# 1_V1.net
KiCad netlist of a schematic drawn in Altium Designer
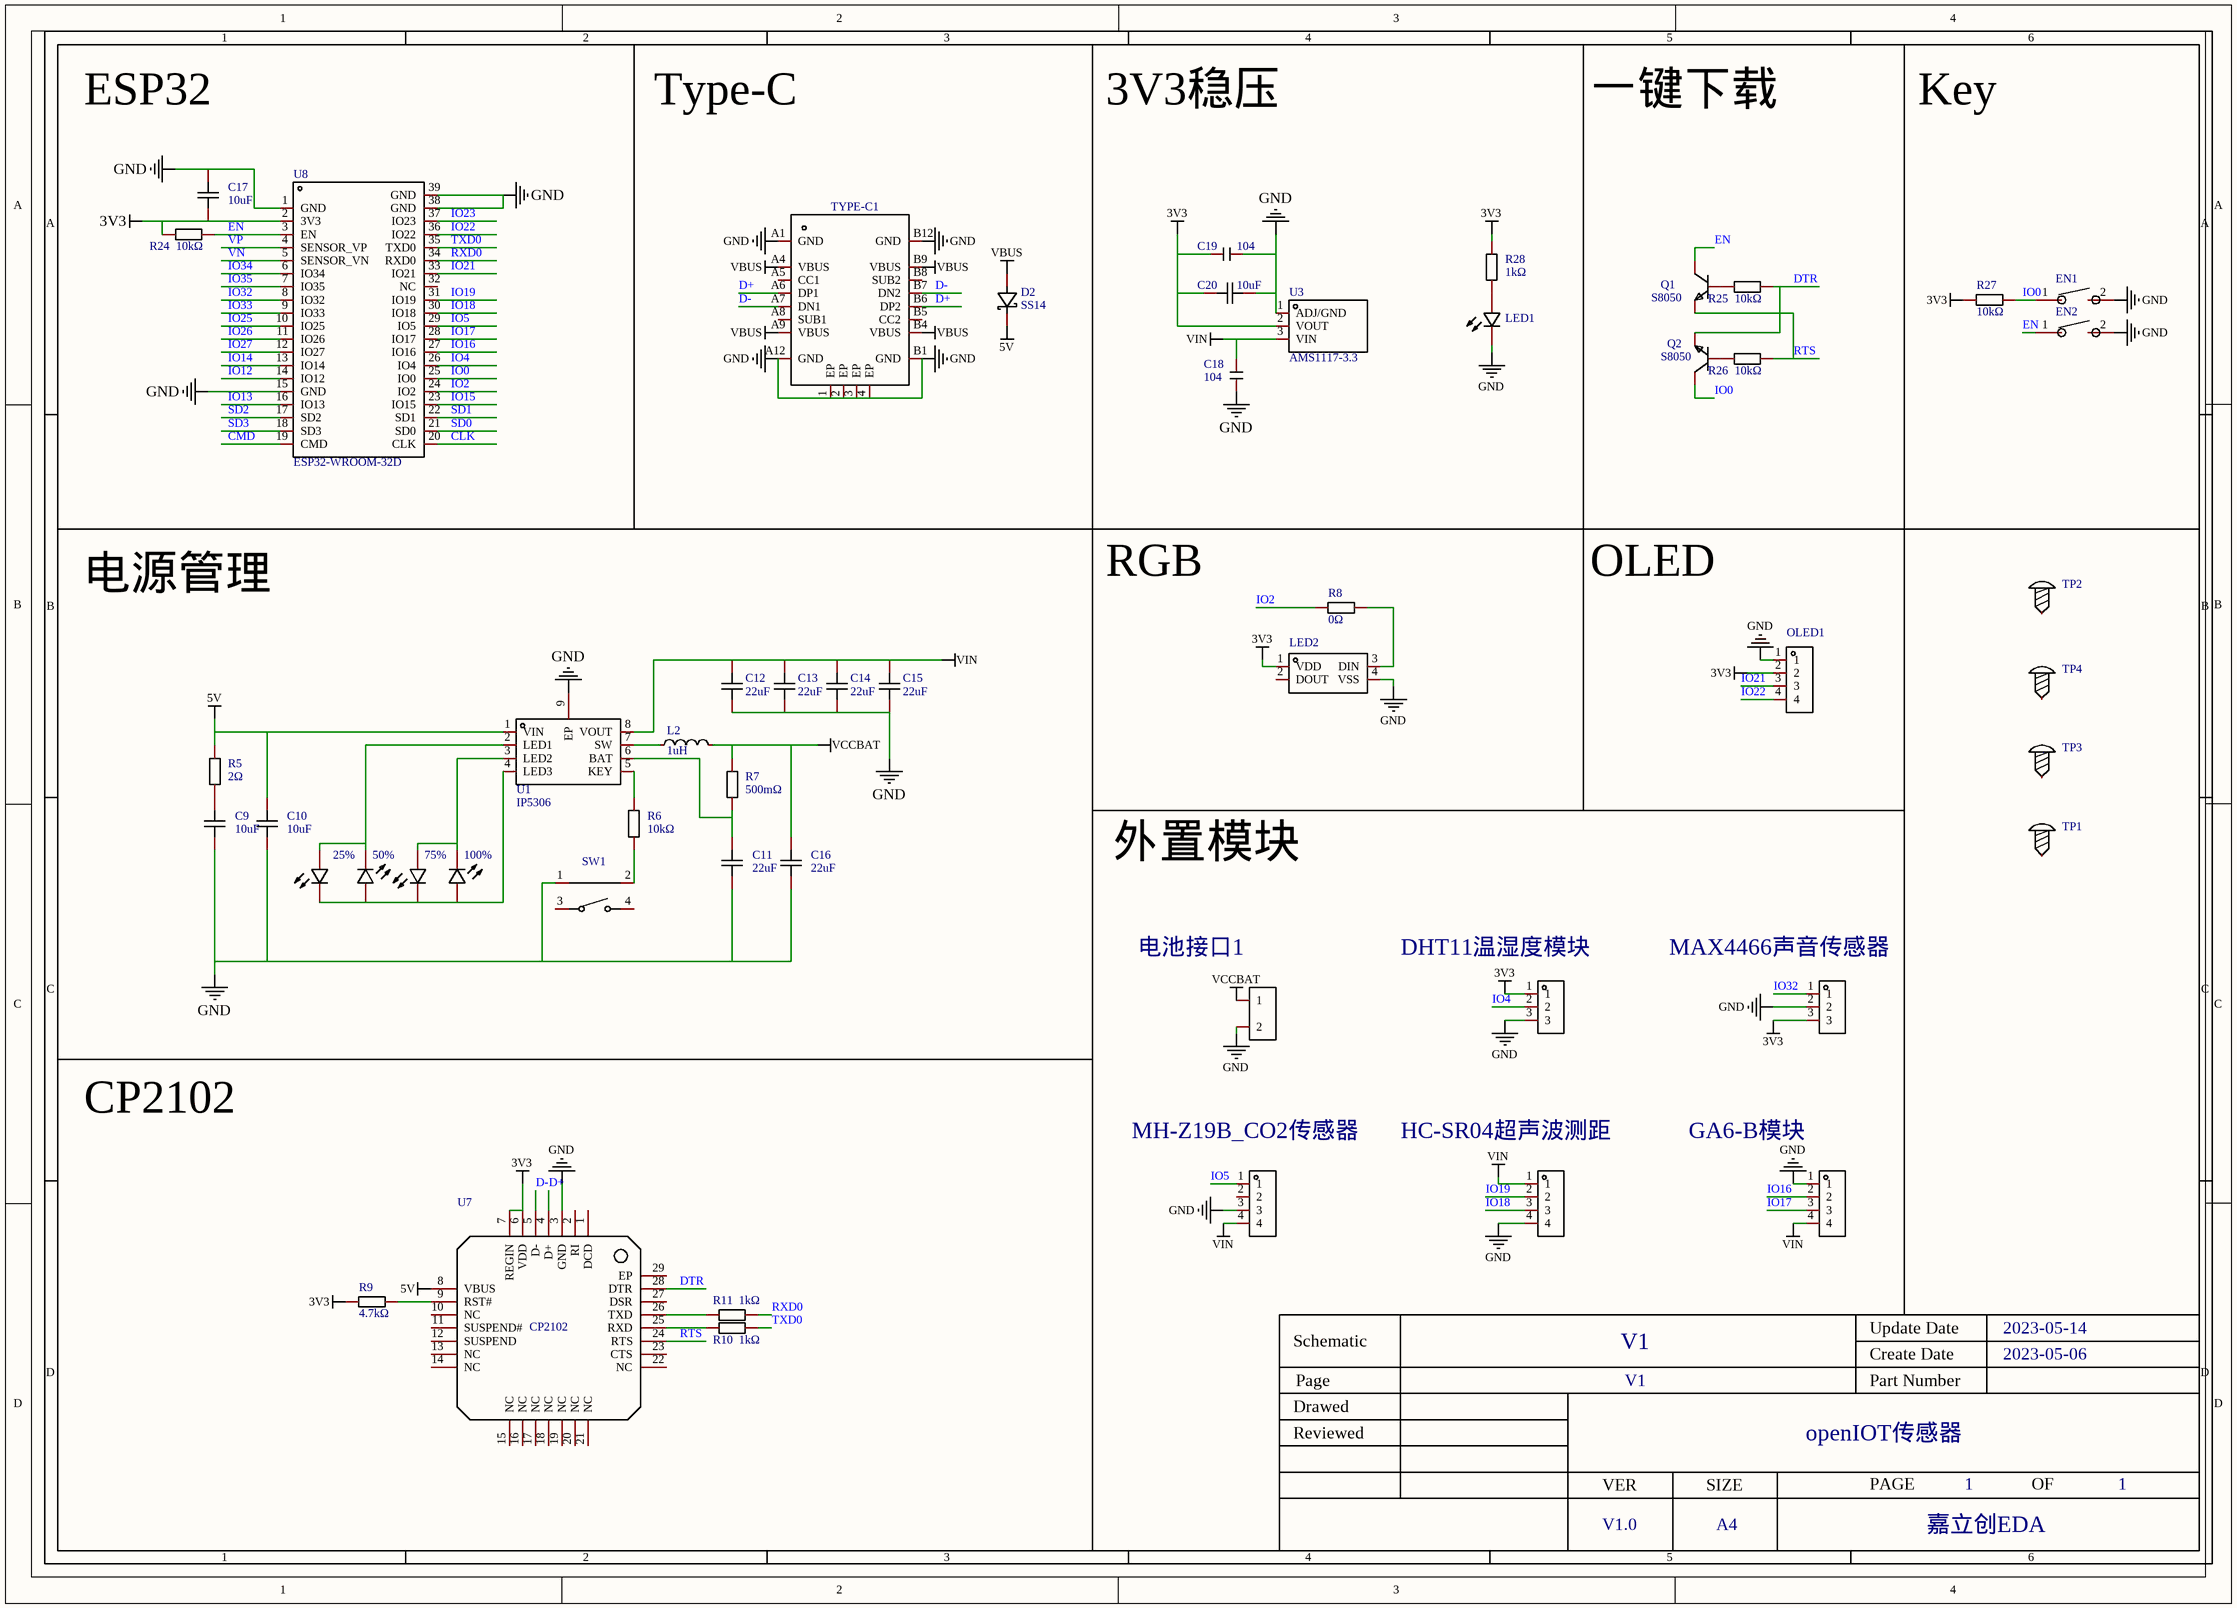
[diagram p0: 1_V1.schdoc]

(export (version "E")
  (design (tool "Eeschema 10.0.6"))
  (components
    (comp (ref "25%")
      (value "19-217/GHC-YR1S2/3T")
      (description "发光颜色:翠绿;二极管配置:-;主波长:520nm~535nm;色温:-;功率:110mW;安装方式:-;")
      (fields (field (name "MANUFACTURER") "EVERLIGHT(亿光)"))
      (libsource (lib "altium-import") (part "root_1_19-217/GHC-YR1S2/3T_"))
    )
    (comp (ref "50%")
      (value "19-217/GHC-YR1S2/3T")
      (description "发光颜色:翠绿;二极管配置:-;主波长:520nm~535nm;色温:-;功率:110mW;安装方式:-;")
      (fields (field (name "MANUFACTURER") "EVERLIGHT(亿光)"))
      (libsource (lib "altium-import") (part "root_3_19-217/GHC-YR1S2/3T_"))
    )
    (comp (ref "75%")
      (value "19-217/GHC-YR1S2/3T")
      (description "发光颜色:翠绿;二极管配置:-;主波长:520nm~535nm;色温:-;功率:110mW;安装方式:-;")
      (fields (field (name "MANUFACTURER") "EVERLIGHT(亿光)"))
      (libsource (lib "altium-import") (part "root_1_19-217/GHC-YR1S2/3T_"))
    )
    (comp (ref "100%")
      (value "19-217/GHC-YR1S2/3T")
      (description "发光颜色:翠绿;二极管配置:-;主波长:520nm~535nm;色温:-;功率:110mW;安装方式:-;")
      (fields (field (name "MANUFACTURER") "EVERLIGHT(亿光)"))
      (libsource (lib "altium-import") (part "root_3_19-217/GHC-YR1S2/3T_"))
    )
    (comp (ref "C9")
      (value "10uF")
      (description "容值:10uF;精度:±10%;额定电压:50V;材质(温度系数):X5R;")
      (fields
        (field (name "NAME") "10uF")
        (field (name "MANUFACTURER") "muRata(村田)")
        (field (name "MANUFACTURER PART") "GRM21BR61H106KE43L")
      )
      (libsource (lib "altium-import") (part "root_1_GRM21BR61H106KE43L_"))
    )
    (comp (ref "C10")
      (value "10uF")
      (description "容值:10uF;精度:±10%;额定电压:50V;材质(温度系数):X5R;")
      (fields
        (field (name "NAME") "10uF")
        (field (name "MANUFACTURER") "muRata(村田)")
        (field (name "MANUFACTURER PART") "GRM21BR61H106KE43L")
      )
      (libsource (lib "altium-import") (part "root_1_GRM21BR61H106KE43L_"))
    )
    (comp (ref "C11")
      (value "22uF")
      (description "容值:22uF;精度:±20%;额定电压:35V;材质(温度系数):X5R;")
      (fields
        (field (name "NAME") "22uF")
        (field (name "MANUFACTURER") "TDK")
        (field (name "MANUFACTURER PART") "C3216X5R1V226MTJ00E")
      )
      (libsource (lib "altium-import") (part "root_0_C3216X5R1V226MTJ00E_"))
    )
    (comp (ref "C12")
      (value "22uF")
      (description "容值:22uF;精度:±20%;额定电压:35V;材质(温度系数):X5R;")
      (fields
        (field (name "NAME") "22uF")
        (field (name "MANUFACTURER") "TDK")
        (field (name "MANUFACTURER PART") "C3216X5R1V226MTJ00E")
      )
      (libsource (lib "altium-import") (part "root_0_C3216X5R1V226MTJ00E_"))
    )
    (comp (ref "C13")
      (value "22uF")
      (description "容值:22uF;精度:±20%;额定电压:35V;材质(温度系数):X5R;")
      (fields
        (field (name "NAME") "22uF")
        (field (name "MANUFACTURER") "TDK")
        (field (name "MANUFACTURER PART") "C3216X5R1V226MTJ00E")
      )
      (libsource (lib "altium-import") (part "root_0_C3216X5R1V226MTJ00E_"))
    )
    (comp (ref "C14")
      (value "22uF")
      (description "容值:22uF;精度:±20%;额定电压:35V;材质(温度系数):X5R;")
      (fields
        (field (name "NAME") "22uF")
        (field (name "MANUFACTURER") "TDK")
        (field (name "MANUFACTURER PART") "C3216X5R1V226MTJ00E")
      )
      (libsource (lib "altium-import") (part "root_0_C3216X5R1V226MTJ00E_"))
    )
    (comp (ref "C15")
      (value "22uF")
      (description "容值:22uF;精度:±20%;额定电压:35V;材质(温度系数):X5R;")
      (fields
        (field (name "NAME") "22uF")
        (field (name "MANUFACTURER") "TDK")
        (field (name "MANUFACTURER PART") "C3216X5R1V226MTJ00E")
      )
      (libsource (lib "altium-import") (part "root_0_C3216X5R1V226MTJ00E_"))
    )
    (comp (ref "C16")
      (value "22uF")
      (description "容值:22uF;精度:±20%;额定电压:35V;材质(温度系数):X5R;")
      (fields
        (field (name "NAME") "22uF")
        (field (name "MANUFACTURER") "TDK")
        (field (name "MANUFACTURER PART") "C3216X5R1V226MTJ00E")
      )
      (libsource (lib "altium-import") (part "root_0_C3216X5R1V226MTJ00E_"))
    )
    (comp (ref "C17")
      (value "10uF")
      (description "容值:10uF;精度:±10%;额定电压:50V;材质(温度系数):X5R;")
      (fields
        (field (name "NAME") "10uF")
        (field (name "MANUFACTURER") "muRata(村田)")
        (field (name "MANUFACTURER PART") "GRM21BR61H106KE43L")
      )
      (libsource (lib "altium-import") (part "root_1_GRM21BR61H106KE43L_"))
    )
    (comp (ref "C18")
      (value "104")
      (fields (field (name "NAME") "104") (field (name "版权归属") "源创客"))
      (libsource (lib "altium-import") (part "root_1_104_"))
    )
    (comp (ref "C19")
      (value "104")
      (fields (field (name "NAME") "104") (field (name "版权归属") "源创客"))
      (libsource (lib "altium-import") (part "root_2_104_"))
    )
    (comp (ref "C20")
      (value "10uF")
      (description "容值:10uF;精度:±10%;额定电压:50V;材质(温度系数):X5R;")
      (fields
        (field (name "NAME") "10uF")
        (field (name "MANUFACTURER") "muRata(村田)")
        (field (name "MANUFACTURER PART") "GRM21BR61H106KE43L")
      )
      (libsource (lib "altium-import") (part "root_2_GRM21BR61H106KE43L_"))
    )
    (comp (ref "D2")
      (value "SS14")
      (description "二极管配置:-;直流反向耐压(Vr):40V;平均整流电流(Io):1A;正向压降(Vf):550mV@1A;反向电流(Ir):500uA@40V;")
      (fields (field (name "NAME") "SS14") (field (name "MANUFACTURER") "KUU"))
      (libsource (lib "altium-import") (part "root_1_SS14_C2909920_"))
    )
    (comp (ref "DHT11温湿度模块")
      (value "B-2200S03P-A120")
      (description "排数:单排;总孔位数:3;间距:2.54mm;插孔结构:1x3P;行距:-;安装类型:直插;塑高:-;触头材质:黄铜;触头镀层:-;")
      (fields (field (name "MANUFACTURER") "Ckmtw(灿科盟)"))
      (libsource (lib "altium-import") (part "root_0_B-2200S03P-A120_"))
    )
    (comp (ref "EN1")
      (value "TSA343G00-250J2")
      (fields (field (name "MANUFACTURER") "BRIGHT(博瑞泰)"))
      (libsource (lib "altium-import") (part "root_0_TSA343G00-250J2_"))
    )
    (comp (ref "EN2")
      (value "TSA343G00-250J2")
      (fields (field (name "MANUFACTURER") "BRIGHT(博瑞泰)"))
      (libsource (lib "altium-import") (part "root_0_TSA343G00-250J2_"))
    )
    (comp (ref "GA6-B模块")
      (value "2.54-1*4P母")
      (fields (field (name "MANUFACTURER") "BOOMELE(博穆精密)"))
      (libsource (lib "altium-import") (part "root_0_2.54-1*4P母_"))
    )
    (comp (ref "HC-SR04超声波测距")
      (value "2.54-1*4P母")
      (fields (field (name "MANUFACTURER") "BOOMELE(博穆精密)"))
      (libsource (lib "altium-import") (part "root_0_2.54-1*4P母_"))
    )
    (comp (ref "L2")
      (value "1uH")
      (description "电感值:1uH;精度:±20%;额定电流:8.5A;饱和电流(Isat):14A;")
      (fields
        (field (name "NAME") "1uH")
        (field (name "MANUFACTURER") "cjiang(长江微电)")
        (field (name "MANUFACTURER PART") "FXL0618-1R0-M")
      )
      (libsource (lib "altium-import") (part "root_0_FXL0618-1R0-M_"))
    )
    (comp (ref "LED1")
      (value "19-217/GHC-YR1S2/3T")
      (description "发光颜色:翠绿;二极管配置:-;主波长:520nm~535nm;色温:-;功率:110mW;安装方式:-;")
      (fields (field (name "MANUFACTURER") "EVERLIGHT(亿光)"))
      (libsource (lib "altium-import") (part "root_1_19-217/GHC-YR1S2/3T_"))
    )
    (comp (ref "LED2")
      (value "WS2812B-V5/W")
      (fields (field (name "MANUFACTURER") "worldsemi"))
      (libsource (lib "altium-import") (part "root_0_WS2812B-V5/W_"))
    )
    (comp (ref "MAX4466声音传感器")
      (value "B-2200S03P-A120")
      (description "排数:单排;总孔位数:3;间距:2.54mm;插孔结构:1x3P;行距:-;安装类型:直插;塑高:-;触头材质:黄铜;触头镀层:-;")
      (fields (field (name "MANUFACTURER") "Ckmtw(灿科盟)"))
      (libsource (lib "altium-import") (part "root_0_B-2200S03P-A120_"))
    )
    (comp (ref "MH-Z19B_CO2传感器")
      (value "2.54-1*4P母")
      (fields (field (name "MANUFACTURER") "BOOMELE(博穆精密)"))
      (libsource (lib "altium-import") (part "root_0_2.54-1*4P母_"))
    )
    (comp (ref "OLED1")
      (value "2.54-1*4P母")
      (fields (field (name "MANUFACTURER") "BOOMELE(博穆精密)"))
      (libsource (lib "altium-import") (part "root_0_2.54-1*4P母_"))
    )
    (comp (ref "Q1")
      (value "S8050")
      (fields (field (name "NAME") "S8050") (field (name "MANUFACTURER") "WPMtek(维攀微)"))
      (libsource (lib "altium-import") (part "root_0_S8050_"))
    )
    (comp (ref "Q2")
      (value "S8050")
      (fields (field (name "NAME") "S8050") (field (name "MANUFACTURER") "WPMtek(维攀微)"))
      (libsource (lib "altium-import") (part "root_2_S8050_"))
    )
    (comp (ref "R5")
      (value "2Ω")
      (description "电阻类型:厚膜电阻;阻值:2Ω;精度:±1%;功率:125mW;")
      (fields
        (field (name "NAME") "2Ω")
        (field (name "MANUFACTURER") "UNI-ROYAL(厚声)")
        (field (name "MANUFACTURER PART") "0805W8F200KT5E")
      )
      (libsource (lib "altium-import") (part "root_1_0805W8F200KT5E_"))
    )
    (comp (ref "R6")
      (value "10kΩ")
      (description "电阻类型:厚膜电阻;阻值:10kΩ;精度:±1%;功率:125mW;")
      (fields
        (field (name "NAME") "10kΩ")
        (field (name "MANUFACTURER") "UNI-ROYAL(厚声)")
        (field (name "MANUFACTURER PART") "0805W8F1002T5E")
      )
      (libsource (lib "altium-import") (part "root_1_0805W8F1002T5E_C17414_"))
    )
    (comp (ref "R7")
      (value "500mΩ")
      (description "电阻类型:厚膜电阻;阻值:500mΩ;精度:±1%;功率:250mW;")
      (fields
        (field (name "NAME") "500mΩ")
        (field (name "MANUFACTURER") "UNI-ROYAL(厚声)")
        (field (name "MANUFACTURER PART") "1206W4F500LT5E")
      )
      (libsource (lib "altium-import") (part "root_1_1206W4F500LT5E_"))
    )
    (comp (ref "R8")
      (value "0Ω")
      (description "电阻类型:厚膜电阻;阻值:0Ω;精度:±1%;功率:100mW;最大工作电压:75V;工作温度范围:-55℃~+155℃;")
      (fields
        (field (name "MANUFACTURER") "UNI-ROYAL(厚声)")
        (field (name "MANUFACTURER PART") "0603WAF0000T5E")
      )
      (libsource (lib "altium-import") (part "root_2_0603WAF0000T5E_"))
    )
    (comp (ref "R9")
      (value "4.7kΩ")
      (description "电阻类型:厚膜电阻;阻值:4.7kΩ;精度:±1%;功率:100mW;")
      (fields
        (field (name "NAME") "4.7kΩ")
        (field (name "MANUFACTURER") "UNI-ROYAL(厚声)")
        (field (name "MANUFACTURER PART") "0603WAF4701T5E")
      )
      (libsource (lib "altium-import") (part "root_0_0603WAF4701T5E_"))
    )
    (comp (ref "R10")
      (value "1kΩ")
      (description "电阻类型:厚膜电阻;阻值:1kΩ;精度:±1%;功率:100mW;")
      (fields
        (field (name "NAME") "1kΩ")
        (field (name "MANUFACTURER") "UNI-ROYAL(厚声)")
        (field (name "MANUFACTURER PART") "0603WAF1001T5E")
      )
      (libsource (lib "altium-import") (part "root_0_0603WAF1001T5E_"))
    )
    (comp (ref "R11")
      (value "1kΩ")
      (description "电阻类型:厚膜电阻;阻值:1kΩ;精度:±1%;功率:100mW;")
      (fields
        (field (name "NAME") "1kΩ")
        (field (name "MANUFACTURER") "UNI-ROYAL(厚声)")
        (field (name "MANUFACTURER PART") "0603WAF1001T5E")
      )
      (libsource (lib "altium-import") (part "root_0_0603WAF1001T5E_"))
    )
    (comp (ref "R24")
      (value "10kΩ")
      (description "电阻类型:厚膜电阻;阻值:10kΩ;精度:±1%;功率:100mW;")
      (fields
        (field (name "NAME") "10kΩ")
        (field (name "MANUFACTURER") "UNI-ROYAL(厚声)")
        (field (name "MANUFACTURER PART") "0603WAF1002T5E")
      )
      (libsource (lib "altium-import") (part "root_0_0603WAF1002T5E_"))
    )
    (comp (ref "R25")
      (value "10kΩ")
      (description "电阻类型:厚膜电阻;阻值:10kΩ;精度:±1%;功率:100mW;")
      (fields
        (field (name "NAME") "10kΩ")
        (field (name "MANUFACTURER") "UNI-ROYAL(厚声)")
        (field (name "MANUFACTURER PART") "0603WAF1002T5E")
      )
      (libsource (lib "altium-import") (part "root_0_0603WAF1002T5E_"))
    )
    (comp (ref "R26")
      (value "10kΩ")
      (description "电阻类型:厚膜电阻;阻值:10kΩ;精度:±1%;功率:100mW;")
      (fields
        (field (name "NAME") "10kΩ")
        (field (name "MANUFACTURER") "UNI-ROYAL(厚声)")
        (field (name "MANUFACTURER PART") "0603WAF1002T5E")
      )
      (libsource (lib "altium-import") (part "root_0_0603WAF1002T5E_"))
    )
    (comp (ref "R27")
      (value "10kΩ")
      (description "电阻类型:厚膜电阻;阻值:10kΩ;精度:±1%;功率:100mW;")
      (fields
        (field (name "NAME") "10kΩ")
        (field (name "MANUFACTURER") "UNI-ROYAL(厚声)")
        (field (name "MANUFACTURER PART") "0603WAF1002T5E")
      )
      (libsource (lib "altium-import") (part "root_2_0603WAF1002T5E_"))
    )
    (comp (ref "R28")
      (value "1kΩ")
      (description "电阻类型:厚膜电阻;阻值:1kΩ;精度:±1%;功率:100mW;")
      (fields
        (field (name "NAME") "1kΩ")
        (field (name "MANUFACTURER") "UNI-ROYAL(厚声)")
        (field (name "MANUFACTURER PART") "0603WAF1001T5E")
      )
      (libsource (lib "altium-import") (part "root_1_0603WAF1001T5E_"))
    )
    (comp (ref "SW1")
      (value "TS24CA")
      (description "触点电流:50mA;额定电压(DC):12V;电路结构:单刀单掷;安装方式:卧贴;带灯:-;机械寿命:-;")
      (fields (field (name "MANUFACTURER") "SHOU HAN(首韩)"))
      (libsource (lib "altium-import") (part "root_0_TS24CA_"))
    )
    (comp (ref "TP1") (value "M2螺丝") (libsource (lib "altium-import") (part "root_0_M2螺丝_")))
    (comp (ref "TP2") (value "M2螺丝") (libsource (lib "altium-import") (part "root_0_M2螺丝_")))
    (comp (ref "TP3") (value "M2螺丝") (libsource (lib "altium-import") (part "root_0_M2螺丝_")))
    (comp (ref "TP4") (value "M2螺丝") (libsource (lib "altium-import") (part "root_0_M2螺丝_")))
    (comp (ref "TYPE-C1")
      (value "KH-TYPE-C-16P")
      (description "连接器类型:Type-C;标准:-;公母:母座;触点数量:16;端口数量:1;安装方式:卧贴;额定电流 - 电源:3A;工作温度范围:-40℃~+85℃;")
      (fields (field (name "MANUFACTURER") "kinghelm(金航标)"))
      (libsource (lib "altium-import") (part "root_0_KH-TYPE-C-16P_"))
    )
    (comp (ref "U1")
      (value "IP5306")
      (description "2.1A充电2.4A放电高集成度移动电源SOC")
      (fields (field (name "NAME") "IP5306") (field (name "MANUFACTURER") "INJOINIC(英集芯)"))
      (libsource (lib "altium-import") (part "root_0_IP5306_"))
    )
    (comp (ref "U3")
      (value "AMS1117-3.3")
      (description "输出类型:-;")
      (fields (field (name "NAME") "AMS1117-3.3") (field (name "MANUFACTURER") "Slkor(萨科微)"))
      (libsource (lib "altium-import") (part "root_0_AMS1117-3.3_C880752_"))
    )
    (comp (ref "U7")
      (value "CP2102")
      (description "类型:Transceiver;协议类别:USB;驱动器/接收器数:1/1;数据速率:1Mbps;")
      (fields (field (name "NAME") "CP2102") (field (name "MANUFACTURER") "SILICON LABS(芯科)"))
      (libsource (lib "altium-import") (part "root_3_CP2102-GMR_"))
    )
    (comp (ref "U8")
      (value "ESP32-WROOM-32D")
      (fields (field (name "NAME") "ESP32-WROOM-32D"))
      (libsource (lib "altium-import") (part "root_0_ESP32-WROOM-32D_"))
    )
    (comp (ref "电池接口1")
      (value "826629-2")
      (fields (field (name "MANUFACTURER") "TE Connectivity(美国泰科)"))
      (libsource (lib "altium-import") (part "root_0_826629-2_"))
    )
  )
  (nets
    (net (code "1") (name "/CLK") (class "Default")
      (node (ref "U8") (pin "20") (pinfunction "CLK_20") (pintype "passive"))
    )
    (net (code "2") (name "/CMD") (class "Default")
      (node (ref "U8") (pin "19") (pinfunction "CMD_19") (pintype "passive"))
    )
    (net (code "3") (name "/D+") (class "Default")
      (node (ref "TYPE-C1") (pin "A6") (pinfunction "DP1_A6") (pintype "passive"))
      (node (ref "TYPE-C1") (pin "B6") (pinfunction "DP2_B6") (pintype "passive"))
      (node (ref "U7") (pin "4") (pinfunction "D+_4") (pintype "passive"))
    )
    (net (code "4") (name "/D-") (class "Default")
      (node (ref "TYPE-C1") (pin "A7") (pinfunction "DN1_A7") (pintype "passive"))
      (node (ref "TYPE-C1") (pin "B7") (pinfunction "DN2_B7") (pintype "passive"))
      (node (ref "U7") (pin "5") (pinfunction "D-_5") (pintype "passive"))
    )
    (net (code "5") (name "/DTR") (class "Default")
      (node (ref "Q2") (pin "2") (pinfunction "E_2") (pintype "passive"))
      (node (ref "R25") (pin "2") (pinfunction "2_2") (pintype "passive"))
      (node (ref "U7") (pin "28") (pinfunction "DTR_28") (pintype "passive"))
    )
    (net (code "6") (name "/EN") (class "Default")
      (node (ref "EN2") (pin "1") (pinfunction "1_1") (pintype "passive"))
      (node (ref "Q1") (pin "3") (pinfunction "C_3") (pintype "passive"))
      (node (ref "R24") (pin "2") (pinfunction "2_2") (pintype "passive"))
      (node (ref "U8") (pin "3") (pinfunction "EN_3") (pintype "passive"))
    )
    (net (code "7") (name "/IO0") (class "Default")
      (node (ref "EN1") (pin "1") (pinfunction "1_1") (pintype "passive"))
      (node (ref "Q2") (pin "3") (pinfunction "C_3") (pintype "passive"))
      (node (ref "R27") (pin "1") (pinfunction "1_1") (pintype "passive"))
      (node (ref "U8") (pin "25") (pinfunction "IO0_25") (pintype "passive"))
    )
    (net (code "8") (name "/IO2") (class "Default")
      (node (ref "R8") (pin "2") (pinfunction "2_2") (pintype "passive"))
      (node (ref "U8") (pin "24") (pinfunction "IO2_24") (pintype "passive"))
    )
    (net (code "9") (name "/IO4") (class "Default")
      (node (ref "DHT11温湿度模块") (pin "2") (pinfunction "2_2") (pintype "passive"))
      (node (ref "U8") (pin "26") (pinfunction "IO4_26") (pintype "passive"))
    )
    (net (code "10") (name "/IO5") (class "Default")
      (node (ref "MH-Z19B_CO2传感器") (pin "1") (pinfunction "1_1") (pintype "passive"))
      (node (ref "U8") (pin "29") (pinfunction "IO5_29") (pintype "passive"))
    )
    (net (code "11") (name "/IO12") (class "Default")
      (node (ref "U8") (pin "14") (pinfunction "IO12_14") (pintype "passive"))
    )
    (net (code "12") (name "/IO13") (class "Default")
      (node (ref "U8") (pin "16") (pinfunction "IO13_16") (pintype "passive"))
    )
    (net (code "13") (name "/IO14") (class "Default")
      (node (ref "U8") (pin "13") (pinfunction "IO14_13") (pintype "passive"))
    )
    (net (code "14") (name "/IO15") (class "Default")
      (node (ref "U8") (pin "23") (pinfunction "IO15_23") (pintype "passive"))
    )
    (net (code "15") (name "/IO16") (class "Default")
      (node (ref "GA6-B模块") (pin "2") (pinfunction "2_2") (pintype "passive"))
      (node (ref "U8") (pin "27") (pinfunction "IO16_27") (pintype "passive"))
    )
    (net (code "16") (name "/IO17") (class "Default")
      (node (ref "GA6-B模块") (pin "3") (pinfunction "3_3") (pintype "passive"))
      (node (ref "U8") (pin "28") (pinfunction "IO17_28") (pintype "passive"))
    )
    (net (code "17") (name "/IO18") (class "Default")
      (node (ref "HC-SR04超声波测距") (pin "3") (pinfunction "3_3") (pintype "passive"))
      (node (ref "U8") (pin "30") (pinfunction "IO18_30") (pintype "passive"))
    )
    (net (code "18") (name "/IO19") (class "Default")
      (node (ref "HC-SR04超声波测距") (pin "2") (pinfunction "2_2") (pintype "passive"))
      (node (ref "U8") (pin "31") (pinfunction "IO19_31") (pintype "passive"))
    )
    (net (code "19") (name "/IO21") (class "Default")
      (node (ref "OLED1") (pin "3") (pinfunction "3_3") (pintype "passive"))
      (node (ref "U8") (pin "33") (pinfunction "IO21_33") (pintype "passive"))
    )
    (net (code "20") (name "/IO22") (class "Default")
      (node (ref "OLED1") (pin "4") (pinfunction "4_4") (pintype "passive"))
      (node (ref "U8") (pin "36") (pinfunction "IO22_36") (pintype "passive"))
    )
    (net (code "21") (name "/IO23") (class "Default")
      (node (ref "U8") (pin "37") (pinfunction "IO23_37") (pintype "passive"))
    )
    (net (code "22") (name "/IO25") (class "Default")
      (node (ref "U8") (pin "10") (pinfunction "IO25_10") (pintype "passive"))
    )
    (net (code "23") (name "/IO26") (class "Default")
      (node (ref "U8") (pin "11") (pinfunction "IO26_11") (pintype "passive"))
    )
    (net (code "24") (name "/IO27") (class "Default")
      (node (ref "U8") (pin "12") (pinfunction "IO27_12") (pintype "passive"))
    )
    (net (code "25") (name "/IO32") (class "Default")
      (node (ref "MAX4466声音传感器") (pin "1") (pinfunction "1_1") (pintype "passive"))
      (node (ref "U8") (pin "8") (pinfunction "IO32_8") (pintype "passive"))
    )
    (net (code "26") (name "/IO33") (class "Default")
      (node (ref "U8") (pin "9") (pinfunction "IO33_9") (pintype "passive"))
    )
    (net (code "27") (name "/IO34") (class "Default")
      (node (ref "U8") (pin "6") (pinfunction "IO34_6") (pintype "passive"))
    )
    (net (code "28") (name "/IO35") (class "Default")
      (node (ref "U8") (pin "7") (pinfunction "IO35_7") (pintype "passive"))
    )
    (net (code "29") (name "/RTS") (class "Default")
      (node (ref "Q1") (pin "2") (pinfunction "E_2") (pintype "passive"))
      (node (ref "R26") (pin "2") (pinfunction "2_2") (pintype "passive"))
      (node (ref "U7") (pin "24") (pinfunction "RTS_24") (pintype "passive"))
    )
    (net (code "30") (name "/RXD0") (class "Default")
      (node (ref "R11") (pin "2") (pinfunction "2_2") (pintype "passive"))
      (node (ref "U8") (pin "34") (pinfunction "RXD0_34") (pintype "passive"))
    )
    (net (code "31") (name "/SD0") (class "Default")
      (node (ref "U8") (pin "21") (pinfunction "SD0_21") (pintype "passive"))
    )
    (net (code "32") (name "/SD1") (class "Default")
      (node (ref "U8") (pin "22") (pinfunction "SD1_22") (pintype "passive"))
    )
    (net (code "33") (name "/SD2") (class "Default")
      (node (ref "U8") (pin "17") (pinfunction "SD2_17") (pintype "passive"))
    )
    (net (code "34") (name "/SD3") (class "Default")
      (node (ref "U8") (pin "18") (pinfunction "SD3_18") (pintype "passive"))
    )
    (net (code "35") (name "/TXD0") (class "Default")
      (node (ref "R10") (pin "2") (pinfunction "2_2") (pintype "passive"))
      (node (ref "U8") (pin "35") (pinfunction "TXD0_35") (pintype "passive"))
    )
    (net (code "36") (name "/VN") (class "Default")
      (node (ref "U8") (pin "5") (pinfunction "SENSOR_VN_5") (pintype "passive"))
    )
    (net (code "37") (name "/VP") (class "Default")
      (node (ref "U8") (pin "4") (pinfunction "SENSOR_VP_4") (pintype "passive"))
    )
    (net (code "38") (name "3V3") (class "Default")
      (node (ref "C17") (pin "1") (pinfunction "1_1") (pintype "passive"))
      (node (ref "C19") (pin "2") (pinfunction "2_2") (pintype "passive"))
      (node (ref "C20") (pin "2") (pinfunction "2_2") (pintype "passive"))
      (node (ref "DHT11温湿度模块") (pin "1") (pinfunction "1_1") (pintype "passive"))
      (node (ref "LED2") (pin "1") (pinfunction "VDD_1") (pintype "passive"))
      (node (ref "MAX4466声音传感器") (pin "3") (pinfunction "3_3") (pintype "passive"))
      (node (ref "OLED1") (pin "2") (pinfunction "2_2") (pintype "passive"))
      (node (ref "R24") (pin "1") (pinfunction "1_1") (pintype "passive"))
      (node (ref "R27") (pin "2") (pinfunction "2_2") (pintype "passive"))
      (node (ref "R28") (pin "2") (pinfunction "2_2") (pintype "passive"))
      (node (ref "R9") (pin "1") (pinfunction "1_1") (pintype "passive"))
      (node (ref "U3") (pin "2") (pinfunction "VOUT_2") (pintype "passive"))
      (node (ref "U7") (pin "6") (pinfunction "VDD_6") (pintype "passive"))
      (node (ref "U7") (pin "7") (pinfunction "REGIN_7") (pintype "passive"))
      (node (ref "U8") (pin "2") (pinfunction "3V3_2") (pintype "passive"))
    )
    (net (code "39") (name "5V") (class "Default")
      (node (ref "C10") (pin "2") (pinfunction "2_2") (pintype "passive"))
      (node (ref "D2") (pin "1") (pinfunction "A_1") (pintype "passive"))
      (node (ref "R5") (pin "2") (pinfunction "2_2") (pintype "passive"))
      (node (ref "U1") (pin "1") (pinfunction "VIN_1") (pintype "passive"))
      (node (ref "U7") (pin "8") (pinfunction "VBUS_8") (pintype "passive"))
    )
    (net (code "40") (name "GND") (class "Default")
      (node (ref "C10") (pin "1") (pinfunction "1_1") (pintype "passive"))
      (node (ref "C11") (pin "1") (pinfunction "1_1") (pintype "passive"))
      (node (ref "C12") (pin "1") (pinfunction "1_1") (pintype "passive"))
      (node (ref "C13") (pin "1") (pinfunction "1_1") (pintype "passive"))
      (node (ref "C14") (pin "1") (pinfunction "1_1") (pintype "passive"))
      (node (ref "C15") (pin "1") (pinfunction "1_1") (pintype "passive"))
      (node (ref "C16") (pin "1") (pinfunction "1_1") (pintype "passive"))
      (node (ref "C17") (pin "2") (pinfunction "2_2") (pintype "passive"))
      (node (ref "C18") (pin "1") (pinfunction "1_1") (pintype "passive"))
      (node (ref "C19") (pin "1") (pinfunction "1_1") (pintype "passive"))
      (node (ref "C20") (pin "1") (pinfunction "1_1") (pintype "passive"))
      (node (ref "C9") (pin "1") (pinfunction "1_1") (pintype "passive"))
      (node (ref "DHT11温湿度模块") (pin "3") (pinfunction "3_3") (pintype "passive"))
      (node (ref "EN1") (pin "2") (pinfunction "2_2") (pintype "passive"))
      (node (ref "EN2") (pin "2") (pinfunction "2_2") (pintype "passive"))
      (node (ref "GA6-B模块") (pin "1") (pinfunction "1_1") (pintype "passive"))
      (node (ref "HC-SR04超声波测距") (pin "4") (pinfunction "4_4") (pintype "passive"))
      (node (ref "LED1") (pin "1") (pinfunction "C_1") (pintype "passive"))
      (node (ref "LED2") (pin "4") (pinfunction "VSS_4") (pintype "passive"))
      (node (ref "MAX4466声音传感器") (pin "2") (pinfunction "2_2") (pintype "passive"))
      (node (ref "MH-Z19B_CO2传感器") (pin "3") (pinfunction "3_3") (pintype "passive"))
      (node (ref "OLED1") (pin "1") (pinfunction "1_1") (pintype "passive"))
      (node (ref "SW1") (pin "1") (pinfunction "1_1") (pintype "passive"))
      (node (ref "TYPE-C1") (pin "1") (pinfunction "EP_1") (pintype "passive"))
      (node (ref "TYPE-C1") (pin "2") (pinfunction "EP_2") (pintype "passive"))
      (node (ref "TYPE-C1") (pin "3") (pinfunction "EP_3") (pintype "passive"))
      (node (ref "TYPE-C1") (pin "4") (pinfunction "EP_4") (pintype "passive"))
      (node (ref "TYPE-C1") (pin "A1") (pinfunction "GND_A1") (pintype "passive"))
      (node (ref "TYPE-C1") (pin "A12") (pinfunction "GND_A12") (pintype "passive"))
      (node (ref "TYPE-C1") (pin "B1") (pinfunction "GND_B1") (pintype "passive"))
      (node (ref "TYPE-C1") (pin "B12") (pinfunction "GND_B12") (pintype "passive"))
      (node (ref "U1") (pin "9") (pinfunction "EP_9") (pintype "passive"))
      (node (ref "U3") (pin "1") (pinfunction "ADJ/GND_1") (pintype "passive"))
      (node (ref "U7") (pin "3") (pinfunction "GND_3") (pintype "passive"))
      (node (ref "U8") (pin "1") (pinfunction "GND_1") (pintype "passive"))
      (node (ref "U8") (pin "15") (pinfunction "GND_15") (pintype "passive"))
      (node (ref "U8") (pin "38") (pinfunction "GND_38") (pintype "passive"))
      (node (ref "U8") (pin "39") (pinfunction "GND_39") (pintype "passive"))
      (node (ref "电池接口1") (pin "2") (pinfunction "2_2") (pintype "passive"))
    )
    (net (code "41") (name "Net-(25%-A)") (class "Default")
      (node (ref "25%") (pin "2") (pinfunction "A_2") (pintype "passive"))
      (node (ref "50%") (pin "1") (pinfunction "C_1") (pintype "passive"))
      (node (ref "U1") (pin "2") (pinfunction "LED1_2") (pintype "passive"))
    )
    (net (code "42") (name "Net-(100%-A)") (class "Default")
      (node (ref "100%") (pin "2") (pinfunction "A_2") (pintype "passive"))
      (node (ref "25%") (pin "1") (pinfunction "C_1") (pintype "passive"))
      (node (ref "50%") (pin "2") (pinfunction "A_2") (pintype "passive"))
      (node (ref "75%") (pin "1") (pinfunction "C_1") (pintype "passive"))
      (node (ref "U1") (pin "4") (pinfunction "LED3_4") (pintype "passive"))
    )
    (net (code "43") (name "Net-(100%-C)") (class "Default")
      (node (ref "100%") (pin "1") (pinfunction "C_1") (pintype "passive"))
      (node (ref "75%") (pin "2") (pinfunction "A_2") (pintype "passive"))
      (node (ref "U1") (pin "3") (pinfunction "LED2_3") (pintype "passive"))
    )
    (net (code "44") (name "Net-(C9-Pad2)") (class "Default")
      (node (ref "C9") (pin "2") (pinfunction "2_2") (pintype "passive"))
      (node (ref "R5") (pin "1") (pinfunction "1_1") (pintype "passive"))
    )
    (net (code "45") (name "Net-(LED1-A)") (class "Default")
      (node (ref "LED1") (pin "2") (pinfunction "A_2") (pintype "passive"))
      (node (ref "R28") (pin "1") (pinfunction "1_1") (pintype "passive"))
    )
    (net (code "46") (name "Net-(LED2-DIN)") (class "Default")
      (node (ref "LED2") (pin "3") (pinfunction "DIN_3") (pintype "passive"))
      (node (ref "R8") (pin "1") (pinfunction "1_1") (pintype "passive"))
    )
    (net (code "47") (name "Net-(Q1-B)") (class "Default")
      (node (ref "Q1") (pin "1") (pinfunction "B_1") (pintype "passive"))
      (node (ref "R25") (pin "1") (pinfunction "1_1") (pintype "passive"))
    )
    (net (code "48") (name "Net-(Q2-B)") (class "Default")
      (node (ref "Q2") (pin "1") (pinfunction "B_1") (pintype "passive"))
      (node (ref "R26") (pin "1") (pinfunction "1_1") (pintype "passive"))
    )
    (net (code "49") (name "Net-(R6-Pad1)") (class "Default")
      (node (ref "R6") (pin "1") (pinfunction "1_1") (pintype "passive"))
      (node (ref "SW1") (pin "2") (pinfunction "2_2") (pintype "passive"))
    )
    (net (code "50") (name "Net-(U1-BAT)") (class "Default")
      (node (ref "C11") (pin "2") (pinfunction "2_2") (pintype "passive"))
      (node (ref "R7") (pin "1") (pinfunction "1_1") (pintype "passive"))
      (node (ref "U1") (pin "6") (pinfunction "BAT_6") (pintype "passive"))
    )
    (net (code "51") (name "Net-(U1-KEY)") (class "Default")
      (node (ref "R6") (pin "2") (pinfunction "2_2") (pintype "passive"))
      (node (ref "U1") (pin "5") (pinfunction "KEY_5") (pintype "passive"))
    )
    (net (code "52") (name "Net-(U1-SW)") (class "Default")
      (node (ref "L2") (pin "1") (pinfunction "1_1") (pintype "passive"))
      (node (ref "U1") (pin "7") (pinfunction "SW_7") (pintype "passive"))
    )
    (net (code "53") (name "Net-(U7-RST#)") (class "Default")
      (node (ref "R9") (pin "2") (pinfunction "2_2") (pintype "passive"))
      (node (ref "U7") (pin "9") (pinfunction "RST#_9") (pintype "passive"))
    )
    (net (code "54") (name "Net-(U7-RXD)") (class "Default")
      (node (ref "R10") (pin "1") (pinfunction "1_1") (pintype "passive"))
      (node (ref "U7") (pin "25") (pinfunction "RXD_25") (pintype "passive"))
    )
    (net (code "55") (name "Net-(U7-TXD)") (class "Default")
      (node (ref "R11") (pin "1") (pinfunction "1_1") (pintype "passive"))
      (node (ref "U7") (pin "26") (pinfunction "TXD_26") (pintype "passive"))
    )
    (net (code "56") (name "VBUS") (class "Default")
      (node (ref "D2") (pin "2") (pinfunction "K_2") (pintype "passive"))
      (node (ref "TYPE-C1") (pin "A4") (pinfunction "VBUS_A4") (pintype "passive"))
      (node (ref "TYPE-C1") (pin "A9") (pinfunction "VBUS_A9") (pintype "passive"))
      (node (ref "TYPE-C1") (pin "B4") (pinfunction "VBUS_B4") (pintype "passive"))
      (node (ref "TYPE-C1") (pin "B9") (pinfunction "VBUS_B9") (pintype "passive"))
    )
    (net (code "57") (name "VCCBAT") (class "Default")
      (node (ref "C16") (pin "2") (pinfunction "2_2") (pintype "passive"))
      (node (ref "L2") (pin "2") (pinfunction "2_2") (pintype "passive"))
      (node (ref "R7") (pin "2") (pinfunction "2_2") (pintype "passive"))
      (node (ref "电池接口1") (pin "1") (pinfunction "1_1") (pintype "passive"))
    )
    (net (code "58") (name "VIN") (class "Default")
      (node (ref "C12") (pin "2") (pinfunction "2_2") (pintype "passive"))
      (node (ref "C13") (pin "2") (pinfunction "2_2") (pintype "passive"))
      (node (ref "C14") (pin "2") (pinfunction "2_2") (pintype "passive"))
      (node (ref "C15") (pin "2") (pinfunction "2_2") (pintype "passive"))
      (node (ref "C18") (pin "2") (pinfunction "2_2") (pintype "passive"))
      (node (ref "GA6-B模块") (pin "4") (pinfunction "4_4") (pintype "passive"))
      (node (ref "HC-SR04超声波测距") (pin "1") (pinfunction "1_1") (pintype "passive"))
      (node (ref "MH-Z19B_CO2传感器") (pin "4") (pinfunction "4_4") (pintype "passive"))
      (node (ref "U1") (pin "8") (pinfunction "VOUT_8") (pintype "passive"))
      (node (ref "U3") (pin "3") (pinfunction "VIN_3") (pintype "passive"))
    )
    (net (code "59") (name "unconnected-(LED2-DOUT-Pad2)") (class "Default")
      (node (ref "LED2") (pin "2") (pinfunction "DOUT_2") (pintype "passive"))
    )
    (net (code "60") (name "unconnected-(MH-Z19B_CO2传感器-Pad2)") (class "Default")
      (node (ref "MH-Z19B_CO2传感器") (pin "2") (pinfunction "2_2") (pintype "passive"))
    )
    (net (code "61") (name "unconnected-(SW1-Pad3)") (class "Default")
      (node (ref "SW1") (pin "3") (pinfunction "3_3") (pintype "passive"))
    )
    (net (code "62") (name "unconnected-(SW1-Pad4)") (class "Default")
      (node (ref "SW1") (pin "4") (pinfunction "4_4") (pintype "passive"))
    )
    (net (code "63") (name "unconnected-(TP1-Pad1)") (class "Default")
      (node (ref "TP1") (pin "1") (pinfunction "1_1") (pintype "passive"))
    )
    (net (code "64") (name "unconnected-(TP2-Pad1)") (class "Default")
      (node (ref "TP2") (pin "1") (pinfunction "1_1") (pintype "passive"))
    )
    (net (code "65") (name "unconnected-(TP3-Pad1)") (class "Default")
      (node (ref "TP3") (pin "1") (pinfunction "1_1") (pintype "passive"))
    )
    (net (code "66") (name "unconnected-(TP4-Pad1)") (class "Default")
      (node (ref "TP4") (pin "1") (pinfunction "1_1") (pintype "passive"))
    )
    (net (code "67") (name "unconnected-(TYPE-C1-CC1-PadA5)") (class "Default")
      (node (ref "TYPE-C1") (pin "A5") (pinfunction "CC1_A5") (pintype "passive"))
    )
    (net (code "68") (name "unconnected-(TYPE-C1-CC2-PadB5)") (class "Default")
      (node (ref "TYPE-C1") (pin "B5") (pinfunction "CC2_B5") (pintype "passive"))
    )
    (net (code "69") (name "unconnected-(TYPE-C1-SUB1-PadA8)") (class "Default")
      (node (ref "TYPE-C1") (pin "A8") (pinfunction "SUB1_A8") (pintype "passive"))
    )
    (net (code "70") (name "unconnected-(TYPE-C1-SUB2-PadB8)") (class "Default")
      (node (ref "TYPE-C1") (pin "B8") (pinfunction "SUB2_B8") (pintype "passive"))
    )
    (net (code "71") (name "unconnected-(U7-CTS-Pad23)") (class "Default")
      (node (ref "U7") (pin "23") (pinfunction "CTS_23") (pintype "passive"))
    )
    (net (code "72") (name "unconnected-(U7-DCD-Pad1)") (class "Default")
      (node (ref "U7") (pin "1") (pinfunction "DCD_1") (pintype "passive"))
    )
    (net (code "73") (name "unconnected-(U7-DSR-Pad27)") (class "Default")
      (node (ref "U7") (pin "27") (pinfunction "DSR_27") (pintype "passive"))
    )
    (net (code "74") (name "unconnected-(U7-EP-Pad29)") (class "Default")
      (node (ref "U7") (pin "29") (pinfunction "EP_29") (pintype "passive"))
    )
    (net (code "75") (name "unconnected-(U7-NC-Pad10)") (class "Default")
      (node (ref "U7") (pin "10") (pinfunction "NC_10") (pintype "passive"))
    )
    (net (code "76") (name "unconnected-(U7-NC-Pad13)") (class "Default")
      (node (ref "U7") (pin "13") (pinfunction "NC_13") (pintype "passive"))
    )
    (net (code "77") (name "unconnected-(U7-NC-Pad14)") (class "Default")
      (node (ref "U7") (pin "14") (pinfunction "NC_14") (pintype "passive"))
    )
    (net (code "78") (name "unconnected-(U7-NC-Pad15)") (class "Default")
      (node (ref "U7") (pin "15") (pinfunction "NC_15") (pintype "passive"))
    )
    (net (code "79") (name "unconnected-(U7-NC-Pad16)") (class "Default")
      (node (ref "U7") (pin "16") (pinfunction "NC_16") (pintype "passive"))
    )
    (net (code "80") (name "unconnected-(U7-NC-Pad17)") (class "Default")
      (node (ref "U7") (pin "17") (pinfunction "NC_17") (pintype "passive"))
    )
    (net (code "81") (name "unconnected-(U7-NC-Pad18)") (class "Default")
      (node (ref "U7") (pin "18") (pinfunction "NC_18") (pintype "passive"))
    )
    (net (code "82") (name "unconnected-(U7-NC-Pad19)") (class "Default")
      (node (ref "U7") (pin "19") (pinfunction "NC_19") (pintype "passive"))
    )
    (net (code "83") (name "unconnected-(U7-NC-Pad20)") (class "Default")
      (node (ref "U7") (pin "20") (pinfunction "NC_20") (pintype "passive"))
    )
    (net (code "84") (name "unconnected-(U7-NC-Pad21)") (class "Default")
      (node (ref "U7") (pin "21") (pinfunction "NC_21") (pintype "passive"))
    )
    (net (code "85") (name "unconnected-(U7-NC-Pad22)") (class "Default")
      (node (ref "U7") (pin "22") (pinfunction "NC_22") (pintype "passive"))
    )
    (net (code "86") (name "unconnected-(U7-RI-Pad2)") (class "Default")
      (node (ref "U7") (pin "2") (pinfunction "RI_2") (pintype "passive"))
    )
    (net (code "87") (name "unconnected-(U7-SUSPEND#-Pad11)") (class "Default")
      (node (ref "U7") (pin "11") (pinfunction "SUSPEND#_11") (pintype "passive"))
    )
    (net (code "88") (name "unconnected-(U7-SUSPEND-Pad12)") (class "Default")
      (node (ref "U7") (pin "12") (pinfunction "SUSPEND_12") (pintype "passive"))
    )
    (net (code "89") (name "unconnected-(U8-NC-Pad32)") (class "Default")
      (node (ref "U8") (pin "32") (pinfunction "NC_32") (pintype "passive"))
    )
  )
)
